# ESP-wroom-02U.net
KiCad netlist of a schematic drawn in EAGLE
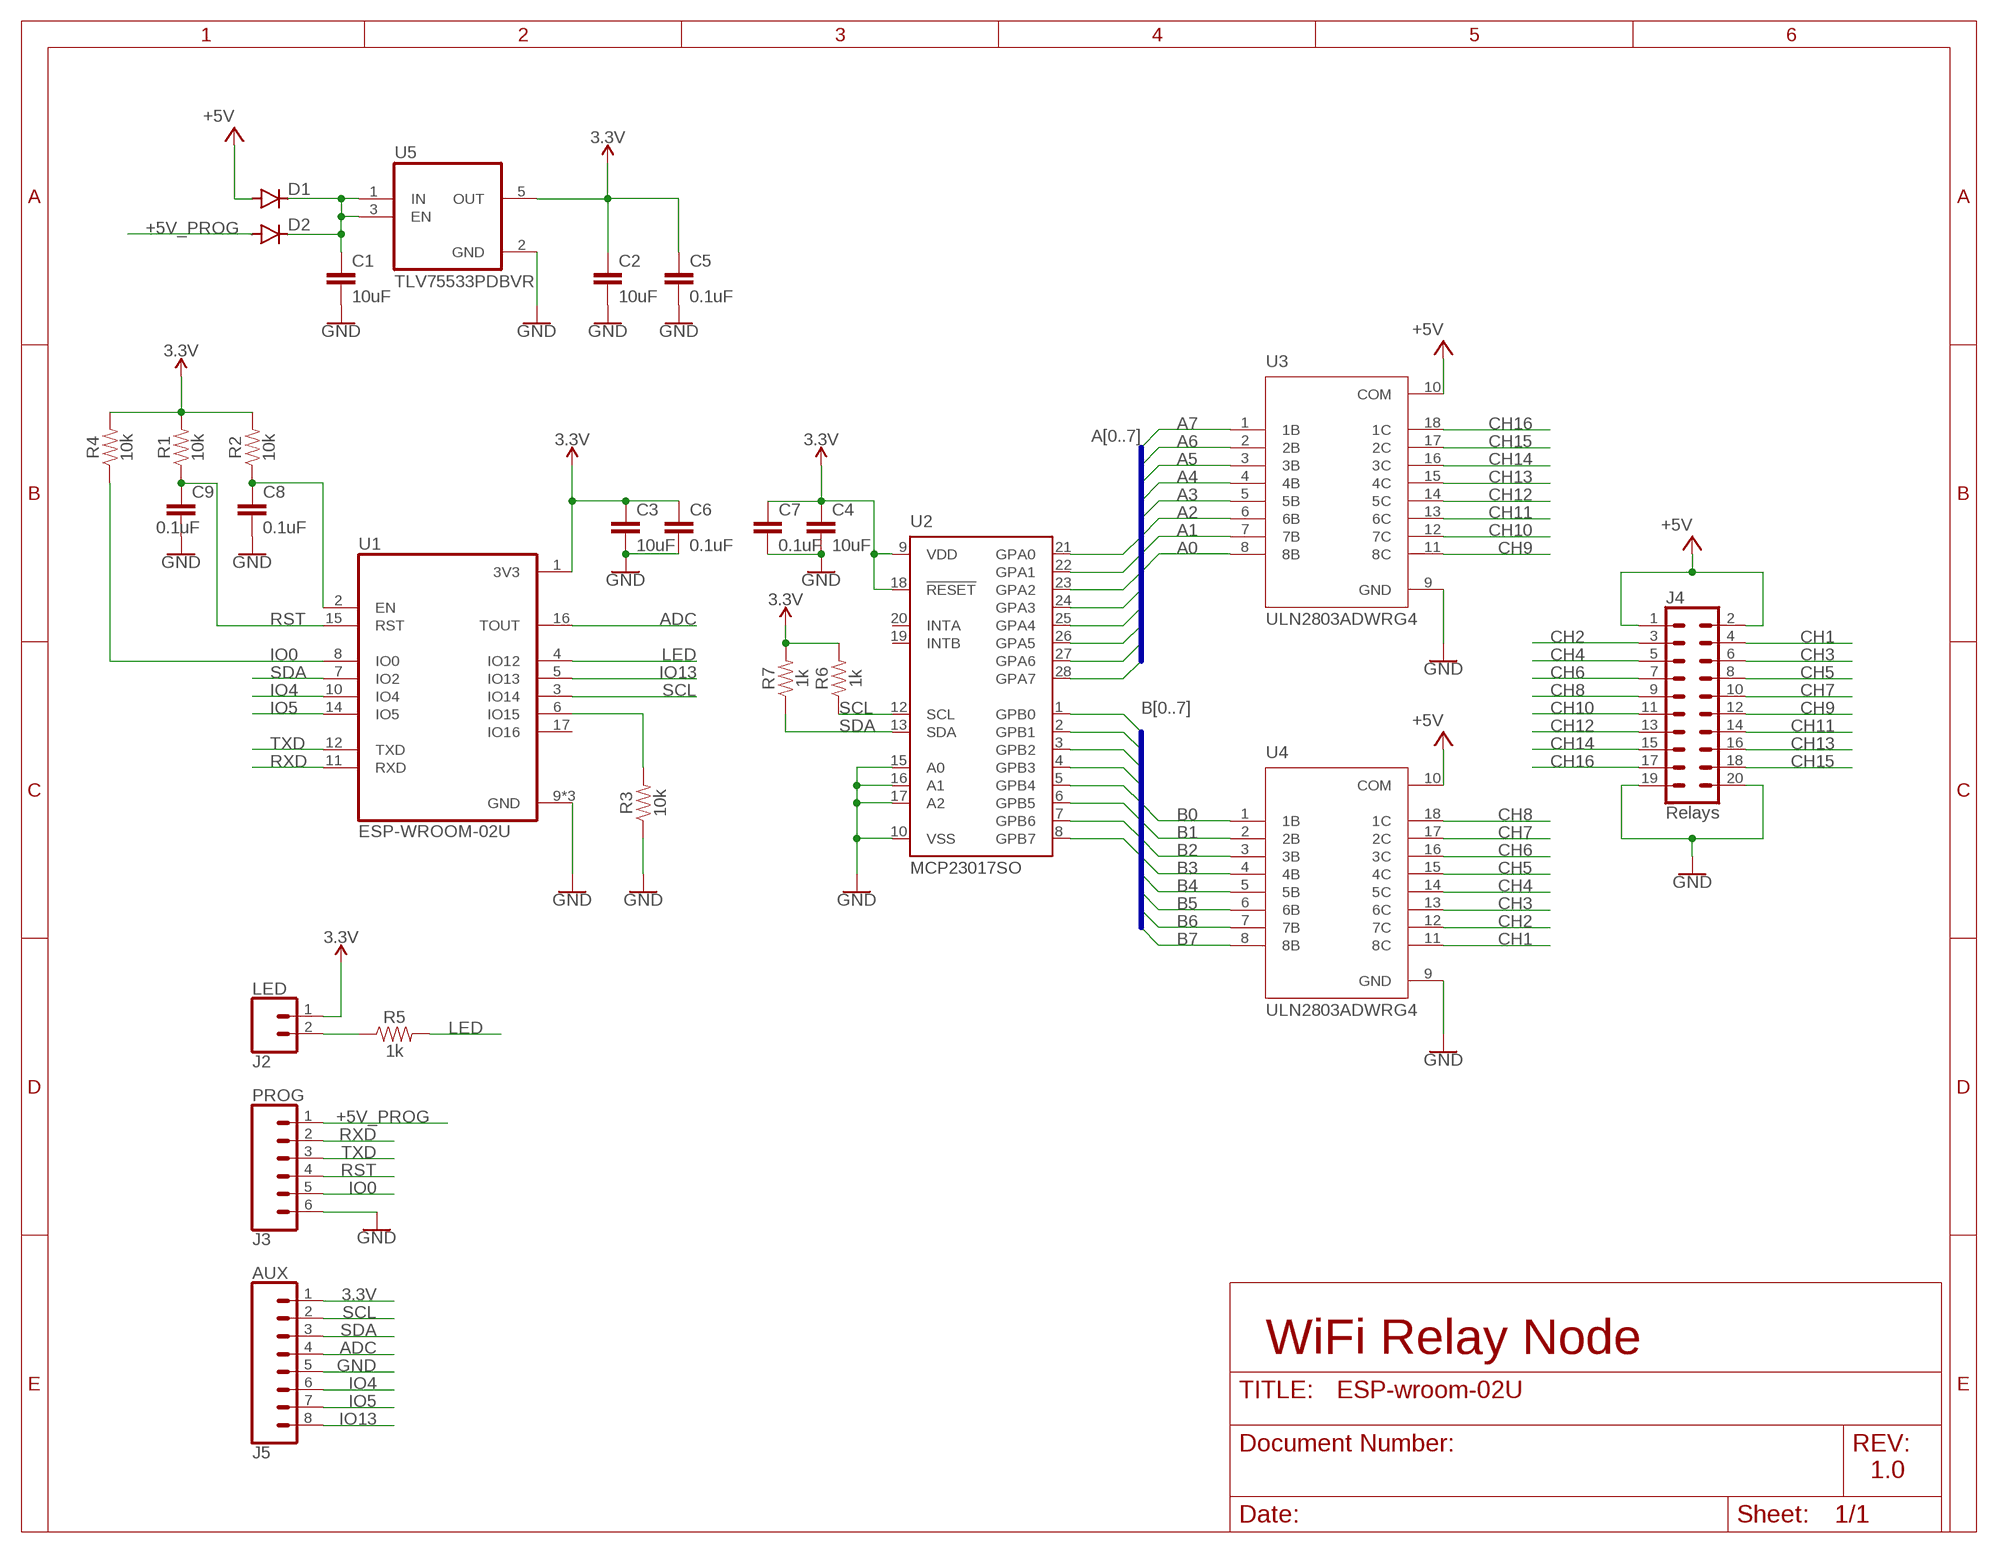
[diagram p0: schematic, sheet 1]

(export (version "E")
  (design (tool "Eeschema 10.0.6"))
  (components
    (comp (ref "C1")
      (value "10uF")
      (footprint "eagle-import:0805")
      (libsource (lib "eagle-import") (part "10UF-0805-25V-10%"))
    )
    (comp (ref "C2")
      (value "10uF")
      (footprint "eagle-import:0805")
      (libsource (lib "eagle-import") (part "10UF-0805-25V-10%"))
    )
    (comp (ref "C3")
      (value "10uF")
      (footprint "eagle-import:0805")
      (libsource (lib "eagle-import") (part "10UF-0805-25V-10%"))
    )
    (comp (ref "C4")
      (value "10uF")
      (footprint "eagle-import:0805")
      (libsource (lib "eagle-import") (part "10UF-0805-25V-10%"))
    )
    (comp (ref "C5")
      (value "0.1uF")
      (footprint "eagle-import:0603")
      (libsource (lib "eagle-import") (part "0.1UF-0603-25V-5%"))
    )
    (comp (ref "C6")
      (value "0.1uF")
      (footprint "eagle-import:0603")
      (libsource (lib "eagle-import") (part "0.1UF-0603-25V-5%"))
    )
    (comp (ref "C7")
      (value "0.1uF")
      (footprint "eagle-import:0603")
      (libsource (lib "eagle-import") (part "0.1UF-0603-25V-5%"))
    )
    (comp (ref "C8")
      (value "0.1uF")
      (footprint "eagle-import:0603")
      (libsource (lib "eagle-import") (part "0.1UF-0603-25V-5%"))
    )
    (comp (ref "C9")
      (value "0.1uF")
      (footprint "eagle-import:0603")
      (libsource (lib "eagle-import") (part "0.1UF-0603-25V-5%"))
    )
    (comp (ref "D1")
      (value "MBR0520LT")
      (footprint "eagle-import:SOD123")
      (libsource (lib "eagle-import") (part "MBR0520LT"))
    )
    (comp (ref "D2")
      (value "MBR0520LT")
      (footprint "eagle-import:SOD123")
      (libsource (lib "eagle-import") (part "MBR0520LT"))
    )
    (comp (ref "J2")
      (value "LED")
      (footprint "eagle-import:1X02")
      (libsource (lib "eagle-import") (part "CONN_02"))
    )
    (comp (ref "J3")
      (value "PROG")
      (footprint "eagle-import:1X06")
      (libsource (lib "eagle-import") (part "CONN_06SILK_FEMALE_PTH"))
    )
    (comp (ref "J4")
      (value "Relays")
      (footprint "eagle-import:2X10")
      (libsource (lib "eagle-import") (part "CONN_10X2"))
    )
    (comp (ref "J5")
      (value "AUX")
      (footprint "eagle-import:1X08")
      (libsource (lib "eagle-import") (part "CONN_08{dblquote}"))
    )
    (comp (ref "R1")
      (value "10k")
      (footprint "eagle-import:0603")
      (libsource (lib "eagle-import") (part "10KOHM-0603-1/10W-5%"))
    )
    (comp (ref "R2")
      (value "10k")
      (footprint "eagle-import:0603")
      (libsource (lib "eagle-import") (part "10KOHM-0603-1/10W-5%"))
    )
    (comp (ref "R3")
      (value "10k")
      (footprint "eagle-import:0603")
      (libsource (lib "eagle-import") (part "10KOHM-0603-1/10W-5%"))
    )
    (comp (ref "R4")
      (value "10k")
      (footprint "eagle-import:0603")
      (libsource (lib "eagle-import") (part "10KOHM-0603-1/10W-5%"))
    )
    (comp (ref "R5")
      (value "1k")
      (footprint "eagle-import:0603")
      (libsource (lib "eagle-import") (part "1KOHM-0603-1/10W-5%"))
    )
    (comp (ref "R6")
      (value "1k")
      (footprint "eagle-import:0603")
      (libsource (lib "eagle-import") (part "1KOHM-0603-1/10W-5%"))
    )
    (comp (ref "R7")
      (value "1k")
      (footprint "eagle-import:0603")
      (libsource (lib "eagle-import") (part "1KOHM-0603-1/10W-5%"))
    )
    (comp (ref "U1")
      (value "ESP-WROOM-02U")
      (footprint "eagle-import:MODULE_ESP-WROOM-02U")
      (fields (field (name "MF") "Espressif Systems"))
      (libsource (lib "eagle-import") (part "ESP-WROOM-02U"))
    )
    (comp (ref "U2")
      (value "MCP23017SO")
      (footprint "eagle-import:SO28W")
      (fields (field (name "MF") "MICROCHIP") (field (name "MPN") "MCP23017-E/SO"))
      (libsource (lib "eagle-import") (part "MCP23017SO"))
    )
    (comp (ref "U3")
      (value "ULN2803ADWRG4")
      (footprint "eagle-import:SOIC127P1030X265-18N")
      (fields (field (name "DIGI-KEY_PART_NUMBER") "296-35964-1-ND") (field (name "MF") "Texas Instruments"))
      (libsource (lib "eagle-import") (part "ULN2803ADWRG4"))
    )
    (comp (ref "U4")
      (value "ULN2803ADWRG4")
      (footprint "eagle-import:SOIC127P1030X265-18N")
      (fields (field (name "DIGI-KEY_PART_NUMBER") "296-35964-1-ND") (field (name "MF") "Texas Instruments"))
      (libsource (lib "eagle-import") (part "ULN2803ADWRG4"))
    )
    (comp (ref "U5")
      (value "TLV75533PDBVR")
      (footprint "eagle-import:SOT95P280X145-5N")
      (fields (field (name "DIGI-KEY_PART_NUMBER") "296-50411-1-ND") (field (name "MF") "Texas Instruments"))
      (libsource (lib "eagle-import") (part "TLV75533PDBVR"))
    )
  )
  (nets
    (net (code "1") (name "+5V") (class "Default")
      (node (ref "D1") (pin "A") (pinfunction "A_A") (pintype "passive"))
      (node (ref "J4") (pin "1") (pinfunction "1_1") (pintype "passive"))
      (node (ref "J4") (pin "2") (pinfunction "2_2") (pintype "passive"))
      (node (ref "U3") (pin "10") (pinfunction "COM_10") (pintype "power_in"))
      (node (ref "U4") (pin "10") (pinfunction "COM_10") (pintype "power_in"))
    )
    (net (code "2") (name "/+5V_PROG") (class "Default")
      (node (ref "D2") (pin "A") (pinfunction "A_A") (pintype "passive"))
      (node (ref "J3") (pin "1") (pinfunction "1_1") (pintype "passive"))
    )
    (net (code "3") (name "/A0") (class "Default")
      (node (ref "U2") (pin "21") (pinfunction "GPA0_21") (pintype "bidirectional"))
      (node (ref "U3") (pin "8") (pinfunction "8B_8") (pintype "input"))
    )
    (net (code "4") (name "/A1") (class "Default")
      (node (ref "U2") (pin "22") (pinfunction "GPA1_22") (pintype "bidirectional"))
      (node (ref "U3") (pin "7") (pinfunction "7B_7") (pintype "input"))
    )
    (net (code "5") (name "/A2") (class "Default")
      (node (ref "U2") (pin "23") (pinfunction "GPA2_23") (pintype "bidirectional"))
      (node (ref "U3") (pin "6") (pinfunction "6B_6") (pintype "input"))
    )
    (net (code "6") (name "/A3") (class "Default")
      (node (ref "U2") (pin "24") (pinfunction "GPA3_24") (pintype "bidirectional"))
      (node (ref "U3") (pin "5") (pinfunction "5B_5") (pintype "input"))
    )
    (net (code "7") (name "/A4") (class "Default")
      (node (ref "U2") (pin "25") (pinfunction "GPA4_25") (pintype "bidirectional"))
      (node (ref "U3") (pin "4") (pinfunction "4B_4") (pintype "input"))
    )
    (net (code "8") (name "/A5") (class "Default")
      (node (ref "U2") (pin "26") (pinfunction "GPA5_26") (pintype "bidirectional"))
      (node (ref "U3") (pin "3") (pinfunction "3B_3") (pintype "input"))
    )
    (net (code "9") (name "/A6") (class "Default")
      (node (ref "U2") (pin "27") (pinfunction "GPA6_27") (pintype "bidirectional"))
      (node (ref "U3") (pin "2") (pinfunction "2B_2") (pintype "input"))
    )
    (net (code "10") (name "/A7") (class "Default")
      (node (ref "U2") (pin "28") (pinfunction "GPA7_28") (pintype "bidirectional"))
      (node (ref "U3") (pin "1") (pinfunction "1B_1") (pintype "input"))
    )
    (net (code "11") (name "/ADC") (class "Default")
      (node (ref "J5") (pin "4") (pinfunction "4_4") (pintype "passive"))
      (node (ref "U1") (pin "16") (pinfunction "TOUT_16") (pintype "bidirectional"))
    )
    (net (code "12") (name "/B0") (class "Default")
      (node (ref "U2") (pin "1") (pinfunction "GPB0_1") (pintype "bidirectional"))
      (node (ref "U4") (pin "1") (pinfunction "1B_1") (pintype "input"))
    )
    (net (code "13") (name "/B1") (class "Default")
      (node (ref "U2") (pin "2") (pinfunction "GPB1_2") (pintype "bidirectional"))
      (node (ref "U4") (pin "2") (pinfunction "2B_2") (pintype "input"))
    )
    (net (code "14") (name "/B2") (class "Default")
      (node (ref "U2") (pin "3") (pinfunction "GPB2_3") (pintype "bidirectional"))
      (node (ref "U4") (pin "3") (pinfunction "3B_3") (pintype "input"))
    )
    (net (code "15") (name "/B3") (class "Default")
      (node (ref "U2") (pin "4") (pinfunction "GPB3_4") (pintype "bidirectional"))
      (node (ref "U4") (pin "4") (pinfunction "4B_4") (pintype "input"))
    )
    (net (code "16") (name "/B4") (class "Default")
      (node (ref "U2") (pin "5") (pinfunction "GPB4_5") (pintype "bidirectional"))
      (node (ref "U4") (pin "5") (pinfunction "5B_5") (pintype "input"))
    )
    (net (code "17") (name "/B5") (class "Default")
      (node (ref "U2") (pin "6") (pinfunction "GPB5_6") (pintype "bidirectional"))
      (node (ref "U4") (pin "6") (pinfunction "6B_6") (pintype "input"))
    )
    (net (code "18") (name "/B6") (class "Default")
      (node (ref "U2") (pin "7") (pinfunction "GPB6_7") (pintype "bidirectional"))
      (node (ref "U4") (pin "7") (pinfunction "7B_7") (pintype "input"))
    )
    (net (code "19") (name "/B7") (class "Default")
      (node (ref "U2") (pin "8") (pinfunction "GPB7_8") (pintype "bidirectional"))
      (node (ref "U4") (pin "8") (pinfunction "8B_8") (pintype "input"))
    )
    (net (code "20") (name "/CH1") (class "Default")
      (node (ref "J4") (pin "4") (pinfunction "4_4") (pintype "passive"))
      (node (ref "U4") (pin "11") (pinfunction "8C_11") (pintype "output"))
    )
    (net (code "21") (name "/CH2") (class "Default")
      (node (ref "J4") (pin "3") (pinfunction "3_3") (pintype "passive"))
      (node (ref "U4") (pin "12") (pinfunction "7C_12") (pintype "output"))
    )
    (net (code "22") (name "/CH3") (class "Default")
      (node (ref "J4") (pin "6") (pinfunction "6_6") (pintype "passive"))
      (node (ref "U4") (pin "13") (pinfunction "6C_13") (pintype "output"))
    )
    (net (code "23") (name "/CH4") (class "Default")
      (node (ref "J4") (pin "5") (pinfunction "5_5") (pintype "passive"))
      (node (ref "U4") (pin "14") (pinfunction "5C_14") (pintype "output"))
    )
    (net (code "24") (name "/CH5") (class "Default")
      (node (ref "J4") (pin "8") (pinfunction "8_8") (pintype "passive"))
      (node (ref "U4") (pin "15") (pinfunction "4C_15") (pintype "output"))
    )
    (net (code "25") (name "/CH6") (class "Default")
      (node (ref "J4") (pin "7") (pinfunction "7_7") (pintype "passive"))
      (node (ref "U4") (pin "16") (pinfunction "3C_16") (pintype "output"))
    )
    (net (code "26") (name "/CH7") (class "Default")
      (node (ref "J4") (pin "10") (pinfunction "10_10") (pintype "passive"))
      (node (ref "U4") (pin "17") (pinfunction "2C_17") (pintype "output"))
    )
    (net (code "27") (name "/CH8") (class "Default")
      (node (ref "J4") (pin "9") (pinfunction "9_9") (pintype "passive"))
      (node (ref "U4") (pin "18") (pinfunction "1C_18") (pintype "output"))
    )
    (net (code "28") (name "/CH9") (class "Default")
      (node (ref "J4") (pin "12") (pinfunction "12_12") (pintype "passive"))
      (node (ref "U3") (pin "11") (pinfunction "8C_11") (pintype "output"))
    )
    (net (code "29") (name "/CH10") (class "Default")
      (node (ref "J4") (pin "11") (pinfunction "11_11") (pintype "passive"))
      (node (ref "U3") (pin "12") (pinfunction "7C_12") (pintype "output"))
    )
    (net (code "30") (name "/CH11") (class "Default")
      (node (ref "J4") (pin "14") (pinfunction "14_14") (pintype "passive"))
      (node (ref "U3") (pin "13") (pinfunction "6C_13") (pintype "output"))
    )
    (net (code "31") (name "/CH12") (class "Default")
      (node (ref "J4") (pin "13") (pinfunction "13_13") (pintype "passive"))
      (node (ref "U3") (pin "14") (pinfunction "5C_14") (pintype "output"))
    )
    (net (code "32") (name "/CH13") (class "Default")
      (node (ref "J4") (pin "16") (pinfunction "16_16") (pintype "passive"))
      (node (ref "U3") (pin "15") (pinfunction "4C_15") (pintype "output"))
    )
    (net (code "33") (name "/CH14") (class "Default")
      (node (ref "J4") (pin "15") (pinfunction "15_15") (pintype "passive"))
      (node (ref "U3") (pin "16") (pinfunction "3C_16") (pintype "output"))
    )
    (net (code "34") (name "/CH15") (class "Default")
      (node (ref "J4") (pin "18") (pinfunction "18_18") (pintype "passive"))
      (node (ref "U3") (pin "17") (pinfunction "2C_17") (pintype "output"))
    )
    (net (code "35") (name "/CH16") (class "Default")
      (node (ref "J4") (pin "17") (pinfunction "17_17") (pintype "passive"))
      (node (ref "U3") (pin "18") (pinfunction "1C_18") (pintype "output"))
    )
    (net (code "36") (name "/IO0") (class "Default")
      (node (ref "J3") (pin "5") (pinfunction "5_5") (pintype "passive"))
      (node (ref "R4") (pin "1") (pinfunction "1_1") (pintype "passive"))
      (node (ref "U1") (pin "8") (pinfunction "IO0_8") (pintype "bidirectional"))
    )
    (net (code "37") (name "/IO4") (class "Default")
      (node (ref "J5") (pin "6") (pinfunction "6_6") (pintype "passive"))
      (node (ref "U1") (pin "10") (pinfunction "IO4_10") (pintype "bidirectional"))
    )
    (net (code "38") (name "/IO5") (class "Default")
      (node (ref "J5") (pin "7") (pinfunction "7_7") (pintype "passive"))
      (node (ref "U1") (pin "14") (pinfunction "IO5_14") (pintype "bidirectional"))
    )
    (net (code "39") (name "/IO13") (class "Default")
      (node (ref "J5") (pin "8") (pinfunction "8_8") (pintype "passive"))
      (node (ref "U1") (pin "5") (pinfunction "IO13_5") (pintype "bidirectional"))
    )
    (net (code "40") (name "/LED") (class "Default")
      (node (ref "R5") (pin "2") (pinfunction "2_2") (pintype "passive"))
      (node (ref "U1") (pin "4") (pinfunction "IO12_4") (pintype "bidirectional"))
    )
    (net (code "41") (name "/RST") (class "Default")
      (node (ref "C9") (pin "1") (pinfunction "1_1") (pintype "passive"))
      (node (ref "J3") (pin "4") (pinfunction "4_4") (pintype "passive"))
      (node (ref "R1") (pin "1") (pinfunction "1_1") (pintype "passive"))
      (node (ref "U1") (pin "15") (pinfunction "RST_15") (pintype "input"))
    )
    (net (code "42") (name "/RXD") (class "Default")
      (node (ref "J3") (pin "2") (pinfunction "2_2") (pintype "passive"))
      (node (ref "U1") (pin "11") (pinfunction "RXD_11") (pintype "bidirectional"))
    )
    (net (code "43") (name "/SCL") (class "Default")
      (node (ref "J5") (pin "2") (pinfunction "2_2") (pintype "passive"))
      (node (ref "R6") (pin "1") (pinfunction "1_1") (pintype "passive"))
      (node (ref "U1") (pin "3") (pinfunction "IO14_3") (pintype "bidirectional"))
      (node (ref "U2") (pin "12") (pinfunction "SCL_12") (pintype "input"))
    )
    (net (code "44") (name "/SDA") (class "Default")
      (node (ref "J5") (pin "3") (pinfunction "3_3") (pintype "passive"))
      (node (ref "R7") (pin "1") (pinfunction "1_1") (pintype "passive"))
      (node (ref "U1") (pin "7") (pinfunction "IO2_7") (pintype "bidirectional"))
      (node (ref "U2") (pin "13") (pinfunction "SDA_13") (pintype "bidirectional"))
    )
    (net (code "45") (name "/TXD") (class "Default")
      (node (ref "J3") (pin "3") (pinfunction "3_3") (pintype "passive"))
      (node (ref "U1") (pin "12") (pinfunction "TXD_12") (pintype "bidirectional"))
    )
    (net (code "46") (name "3.3V") (class "Default")
      (node (ref "C2") (pin "1") (pinfunction "1_1") (pintype "passive"))
      (node (ref "C3") (pin "1") (pinfunction "1_1") (pintype "passive"))
      (node (ref "C4") (pin "1") (pinfunction "1_1") (pintype "passive"))
      (node (ref "C5") (pin "1") (pinfunction "1_1") (pintype "passive"))
      (node (ref "C6") (pin "1") (pinfunction "1_1") (pintype "passive"))
      (node (ref "C7") (pin "1") (pinfunction "1_1") (pintype "passive"))
      (node (ref "J2") (pin "1") (pinfunction "1_1") (pintype "passive"))
      (node (ref "J5") (pin "1") (pinfunction "1_1") (pintype "passive"))
      (node (ref "R1") (pin "2") (pinfunction "2_2") (pintype "passive"))
      (node (ref "R2") (pin "2") (pinfunction "2_2") (pintype "passive"))
      (node (ref "R4") (pin "2") (pinfunction "2_2") (pintype "passive"))
      (node (ref "R6") (pin "2") (pinfunction "2_2") (pintype "passive"))
      (node (ref "R7") (pin "2") (pinfunction "2_2") (pintype "passive"))
      (node (ref "U1") (pin "1") (pinfunction "3V3_1") (pintype "power_in"))
      (node (ref "U2") (pin "18") (pinfunction "~{RESET}_18") (pintype "input"))
      (node (ref "U2") (pin "9") (pinfunction "VDD_9") (pintype "power_in"))
      (node (ref "U5") (pin "5") (pinfunction "OUT_5") (pintype "power_in"))
    )
    (net (code "47") (name "GND") (class "Default")
      (node (ref "C1") (pin "2") (pinfunction "2_2") (pintype "passive"))
      (node (ref "C2") (pin "2") (pinfunction "2_2") (pintype "passive"))
      (node (ref "C3") (pin "2") (pinfunction "2_2") (pintype "passive"))
      (node (ref "C4") (pin "2") (pinfunction "2_2") (pintype "passive"))
      (node (ref "C5") (pin "2") (pinfunction "2_2") (pintype "passive"))
      (node (ref "C6") (pin "2") (pinfunction "2_2") (pintype "passive"))
      (node (ref "C7") (pin "2") (pinfunction "2_2") (pintype "passive"))
      (node (ref "C8") (pin "2") (pinfunction "2_2") (pintype "passive"))
      (node (ref "C9") (pin "2") (pinfunction "2_2") (pintype "passive"))
      (node (ref "J3") (pin "6") (pinfunction "6_6") (pintype "passive"))
      (node (ref "J4") (pin "19") (pinfunction "19_19") (pintype "passive"))
      (node (ref "J4") (pin "20") (pinfunction "20_20") (pintype "passive"))
      (node (ref "J5") (pin "5") (pinfunction "5_5") (pintype "passive"))
      (node (ref "R3") (pin "1") (pinfunction "1_1") (pintype "passive"))
      (node (ref "U1") (pin "13") (pinfunction "GND_13") (pintype "power_in"))
      (node (ref "U1") (pin "18") (pinfunction "GND_18") (pintype "power_in"))
      (node (ref "U1") (pin "9") (pinfunction "GND_9") (pintype "power_in"))
      (node (ref "U2") (pin "10") (pinfunction "VSS_10") (pintype "power_in"))
      (node (ref "U2") (pin "15") (pinfunction "A0_15") (pintype "input"))
      (node (ref "U2") (pin "16") (pinfunction "A1_16") (pintype "input"))
      (node (ref "U2") (pin "17") (pinfunction "A2_17") (pintype "input"))
      (node (ref "U3") (pin "9") (pinfunction "GND_9") (pintype "power_in"))
      (node (ref "U4") (pin "9") (pinfunction "GND_9") (pintype "power_in"))
      (node (ref "U5") (pin "2") (pinfunction "GND_2") (pintype "power_in"))
    )
    (net (code "48") (name "Net-(J2-Pad2)") (class "Default")
      (node (ref "J2") (pin "2") (pinfunction "2_2") (pintype "passive"))
      (node (ref "R5") (pin "1") (pinfunction "1_1") (pintype "passive"))
    )
    (net (code "49") (name "Net-(U1-EN)") (class "Default")
      (node (ref "C8") (pin "1") (pinfunction "1_1") (pintype "passive"))
      (node (ref "R2") (pin "1") (pinfunction "1_1") (pintype "passive"))
      (node (ref "U1") (pin "2") (pinfunction "EN_2") (pintype "input"))
    )
    (net (code "50") (name "Net-(U1-IO15)") (class "Default")
      (node (ref "R3") (pin "2") (pinfunction "2_2") (pintype "passive"))
      (node (ref "U1") (pin "6") (pinfunction "IO15_6") (pintype "bidirectional"))
    )
    (net (code "51") (name "Net-(U5-EN)") (class "Default")
      (node (ref "C1") (pin "1") (pinfunction "1_1") (pintype "passive"))
      (node (ref "D1") (pin "C") (pinfunction "C_C") (pintype "passive"))
      (node (ref "D2") (pin "C") (pinfunction "C_C") (pintype "passive"))
      (node (ref "U5") (pin "1") (pinfunction "IN_1") (pintype "input"))
      (node (ref "U5") (pin "3") (pinfunction "EN_3") (pintype "input"))
    )
    (net (code "52") (name "unconnected-(U1-IO16-Pad17)") (class "Default")
      (node (ref "U1") (pin "17") (pinfunction "IO16_17") (pintype "bidirectional"))
    )
    (net (code "53") (name "unconnected-(U2-INTA-Pad20)") (class "Default")
      (node (ref "U2") (pin "20") (pinfunction "INTA_20") (pintype "output"))
    )
    (net (code "54") (name "unconnected-(U2-INTB-Pad19)") (class "Default")
      (node (ref "U2") (pin "19") (pinfunction "INTB_19") (pintype "output"))
    )
  )
)
